# power_supply_pcb.net
KiCad netlist of a schematic drawn in EasyEDA
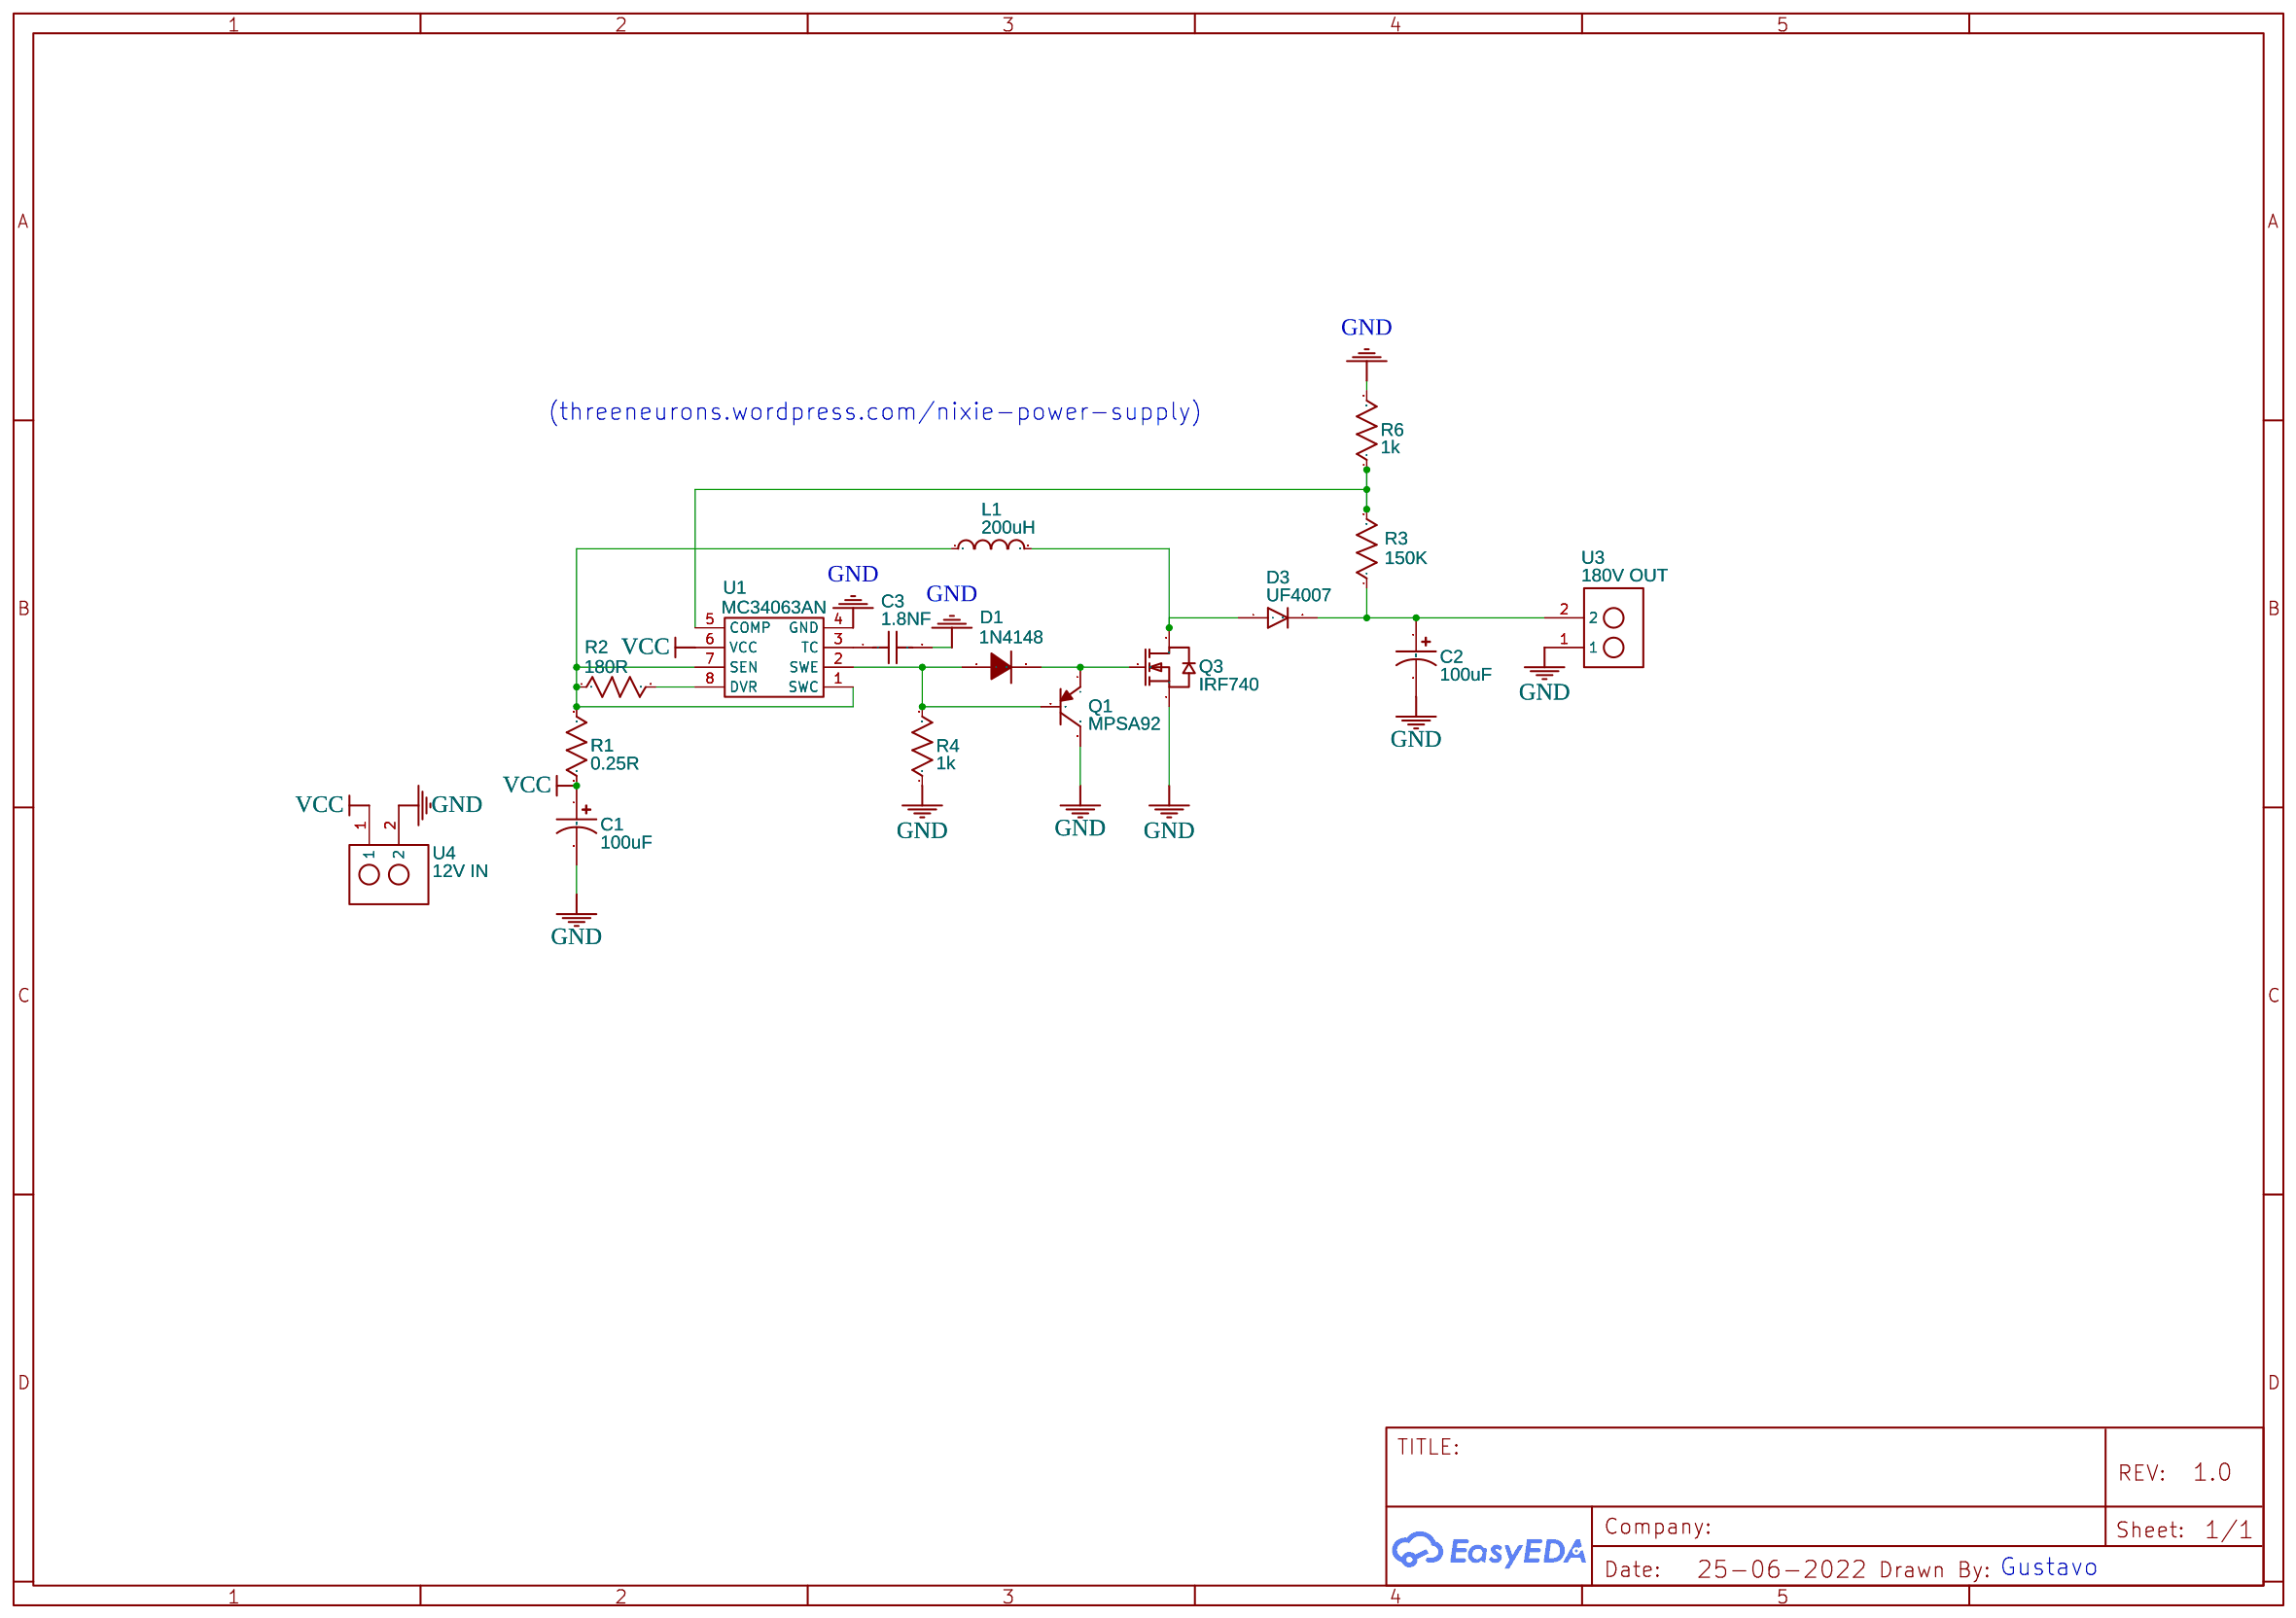
[diagram p0: schematic sheet]

(export (version "E")
  (design (tool "Eeschema 10.0.6"))
  (components
    (comp (ref "C1") (value "100uF") (libsource (lib "") (part "CE_TH_D5.0×F2.0_US")))
    (comp (ref "C2") (value "100uF") (libsource (lib "") (part "CE_TH_D12.5×F5.0_US")))
    (comp (ref "C3") (value "1.8NF") (libsource (lib "") (part "C_RAD-0.1_US")))
    (comp (ref "D1")
      (value "1N4148")
      (fields (field (name "BOM_Supplier Part") "C14516"))
      (libsource (lib "") (part "1N4148"))
    )
    (comp (ref "D3")
      (value "UF4007")
      (fields (field (name "BOM_Supplier Part") "C84067"))
      (libsource (lib "") (part "UF4007_C84067"))
    )
    (comp (ref "L1") (value "200uH") (libsource (lib "") (part "L_AXIAL-0.6_US")))
    (comp (ref "Q1")
      (value "MPSA92")
      (fields (field (name "BOM_Supplier Part") "C118558"))
      (libsource (lib "") (part "MPSA92"))
    )
    (comp (ref "Q3")
      (value "IRF740")
      (fields (field (name "BOM_Supplier Part") "C358408"))
      (libsource (lib "") (part "IRF740"))
    )
    (comp (ref "R1") (value "0.25R") (libsource (lib "") (part "R_AXIAL-0.4_US")))
    (comp (ref "R2") (value "180R") (libsource (lib "") (part "R_AXIAL-0.4_US_1")))
    (comp (ref "R3") (value "150K") (libsource (lib "") (part "R_AXIAL-0.4_US")))
    (comp (ref "R4") (value "1k") (libsource (lib "") (part "R_AXIAL-0.4_US")))
    (comp (ref "R6") (value "1k") (libsource (lib "") (part "R_AXIAL-0.4_US")))
    (comp (ref "U1")
      (value "MC34063AN")
      (fields (field (name "BOM_Supplier Part") "C126078"))
      (libsource (lib "") (part "MC34063AN"))
    )
    (comp (ref "U3") (value "180V OUT") (libsource (lib "") (part "2 pin terminal_1")))
    (comp (ref "U4") (value "12V IN") (libsource (lib "") (part "2 pin terminal")))
  )
  (nets
    (net (code "1") (name "GND") (class "Default")
      (node (ref "C1") (pin "2") (pinfunction "2_2") (pintype "unspecified"))
      (node (ref "C2") (pin "2") (pinfunction "2_2") (pintype "unspecified"))
      (node (ref "C3") (pin "2") (pinfunction "2_2") (pintype "unspecified"))
      (node (ref "Q1") (pin "3") (pinfunction "3_3") (pintype "input"))
      (node (ref "Q3") (pin "3") (pinfunction "S_3") (pintype "unspecified"))
      (node (ref "R4") (pin "1") (pinfunction "1_1") (pintype "unspecified"))
      (node (ref "R6") (pin "2") (pinfunction "2_2") (pintype "unspecified"))
      (node (ref "U1") (pin "4") (pinfunction "GND_4") (pintype "unspecified"))
      (node (ref "U3") (pin "1") (pinfunction "1_1") (pintype "unspecified"))
      (node (ref "U4") (pin "2") (pinfunction "2_2") (pintype "unspecified"))
    )
    (net (code "2") (name "Net-(D1-A)") (class "Default")
      (node (ref "D1") (pin "1") (pinfunction "A_1") (pintype "unspecified"))
      (node (ref "Q1") (pin "2") (pinfunction "2_2") (pintype "input"))
      (node (ref "R4") (pin "2") (pinfunction "2_2") (pintype "unspecified"))
      (node (ref "U1") (pin "2") (pinfunction "SWE_2") (pintype "unspecified"))
    )
    (net (code "3") (name "Net-(D1-C)") (class "Default")
      (node (ref "D1") (pin "2") (pinfunction "C_2") (pintype "unspecified"))
      (node (ref "Q1") (pin "1") (pinfunction "1_1") (pintype "input"))
      (node (ref "Q3") (pin "1") (pinfunction "G_1") (pintype "unspecified"))
    )
    (net (code "4") (name "Net-(D3-A)") (class "Default")
      (node (ref "D3") (pin "1") (pinfunction "A_1") (pintype "unspecified"))
      (node (ref "L1") (pin "2") (pinfunction "2_2") (pintype "unspecified"))
      (node (ref "Q3") (pin "2") (pinfunction "D_2") (pintype "unspecified"))
    )
    (net (code "5") (name "Net-(D3-C)") (class "Default")
      (node (ref "C2") (pin "1") (pinfunction "1_1") (pintype "unspecified"))
      (node (ref "D3") (pin "2") (pinfunction "C_2") (pintype "unspecified"))
      (node (ref "R3") (pin "1") (pinfunction "1_1") (pintype "unspecified"))
      (node (ref "U3") (pin "2") (pinfunction "2_2") (pintype "unspecified"))
    )
    (net (code "6") (name "Net-(U1-COMP)") (class "Default")
      (node (ref "R3") (pin "2") (pinfunction "2_2") (pintype "unspecified"))
      (node (ref "R6") (pin "1") (pinfunction "1_1") (pintype "unspecified"))
      (node (ref "U1") (pin "5") (pinfunction "COMP_5") (pintype "unspecified"))
    )
    (net (code "7") (name "Net-(U1-DVR)") (class "Default")
      (node (ref "R2") (pin "2") (pinfunction "2_2") (pintype "unspecified"))
      (node (ref "U1") (pin "8") (pinfunction "DVR_8") (pintype "unspecified"))
    )
    (net (code "8") (name "Net-(U1-SEN)") (class "Default")
      (node (ref "L1") (pin "1") (pinfunction "1_1") (pintype "unspecified"))
      (node (ref "R1") (pin "2") (pinfunction "2_2") (pintype "unspecified"))
      (node (ref "R2") (pin "1") (pinfunction "1_1") (pintype "unspecified"))
      (node (ref "U1") (pin "1") (pinfunction "SWC_1") (pintype "unspecified"))
      (node (ref "U1") (pin "7") (pinfunction "SEN_7") (pintype "unspecified"))
    )
    (net (code "9") (name "Net-(U1-TC)") (class "Default")
      (node (ref "C3") (pin "1") (pinfunction "1_1") (pintype "unspecified"))
      (node (ref "U1") (pin "3") (pinfunction "TC_3") (pintype "unspecified"))
    )
    (net (code "10") (name "VCC") (class "Default")
      (node (ref "C1") (pin "1") (pinfunction "1_1") (pintype "unspecified"))
      (node (ref "R1") (pin "1") (pinfunction "1_1") (pintype "unspecified"))
      (node (ref "U1") (pin "6") (pinfunction "VCC_6") (pintype "unspecified"))
      (node (ref "U4") (pin "1") (pinfunction "1_1") (pintype "unspecified"))
    )
  )
)
